# ALLPRINT-CAPBOARD-677512-DIGITAL-OUTPUTS.net
KiCad netlist of a schematic drawn in Altium Designer
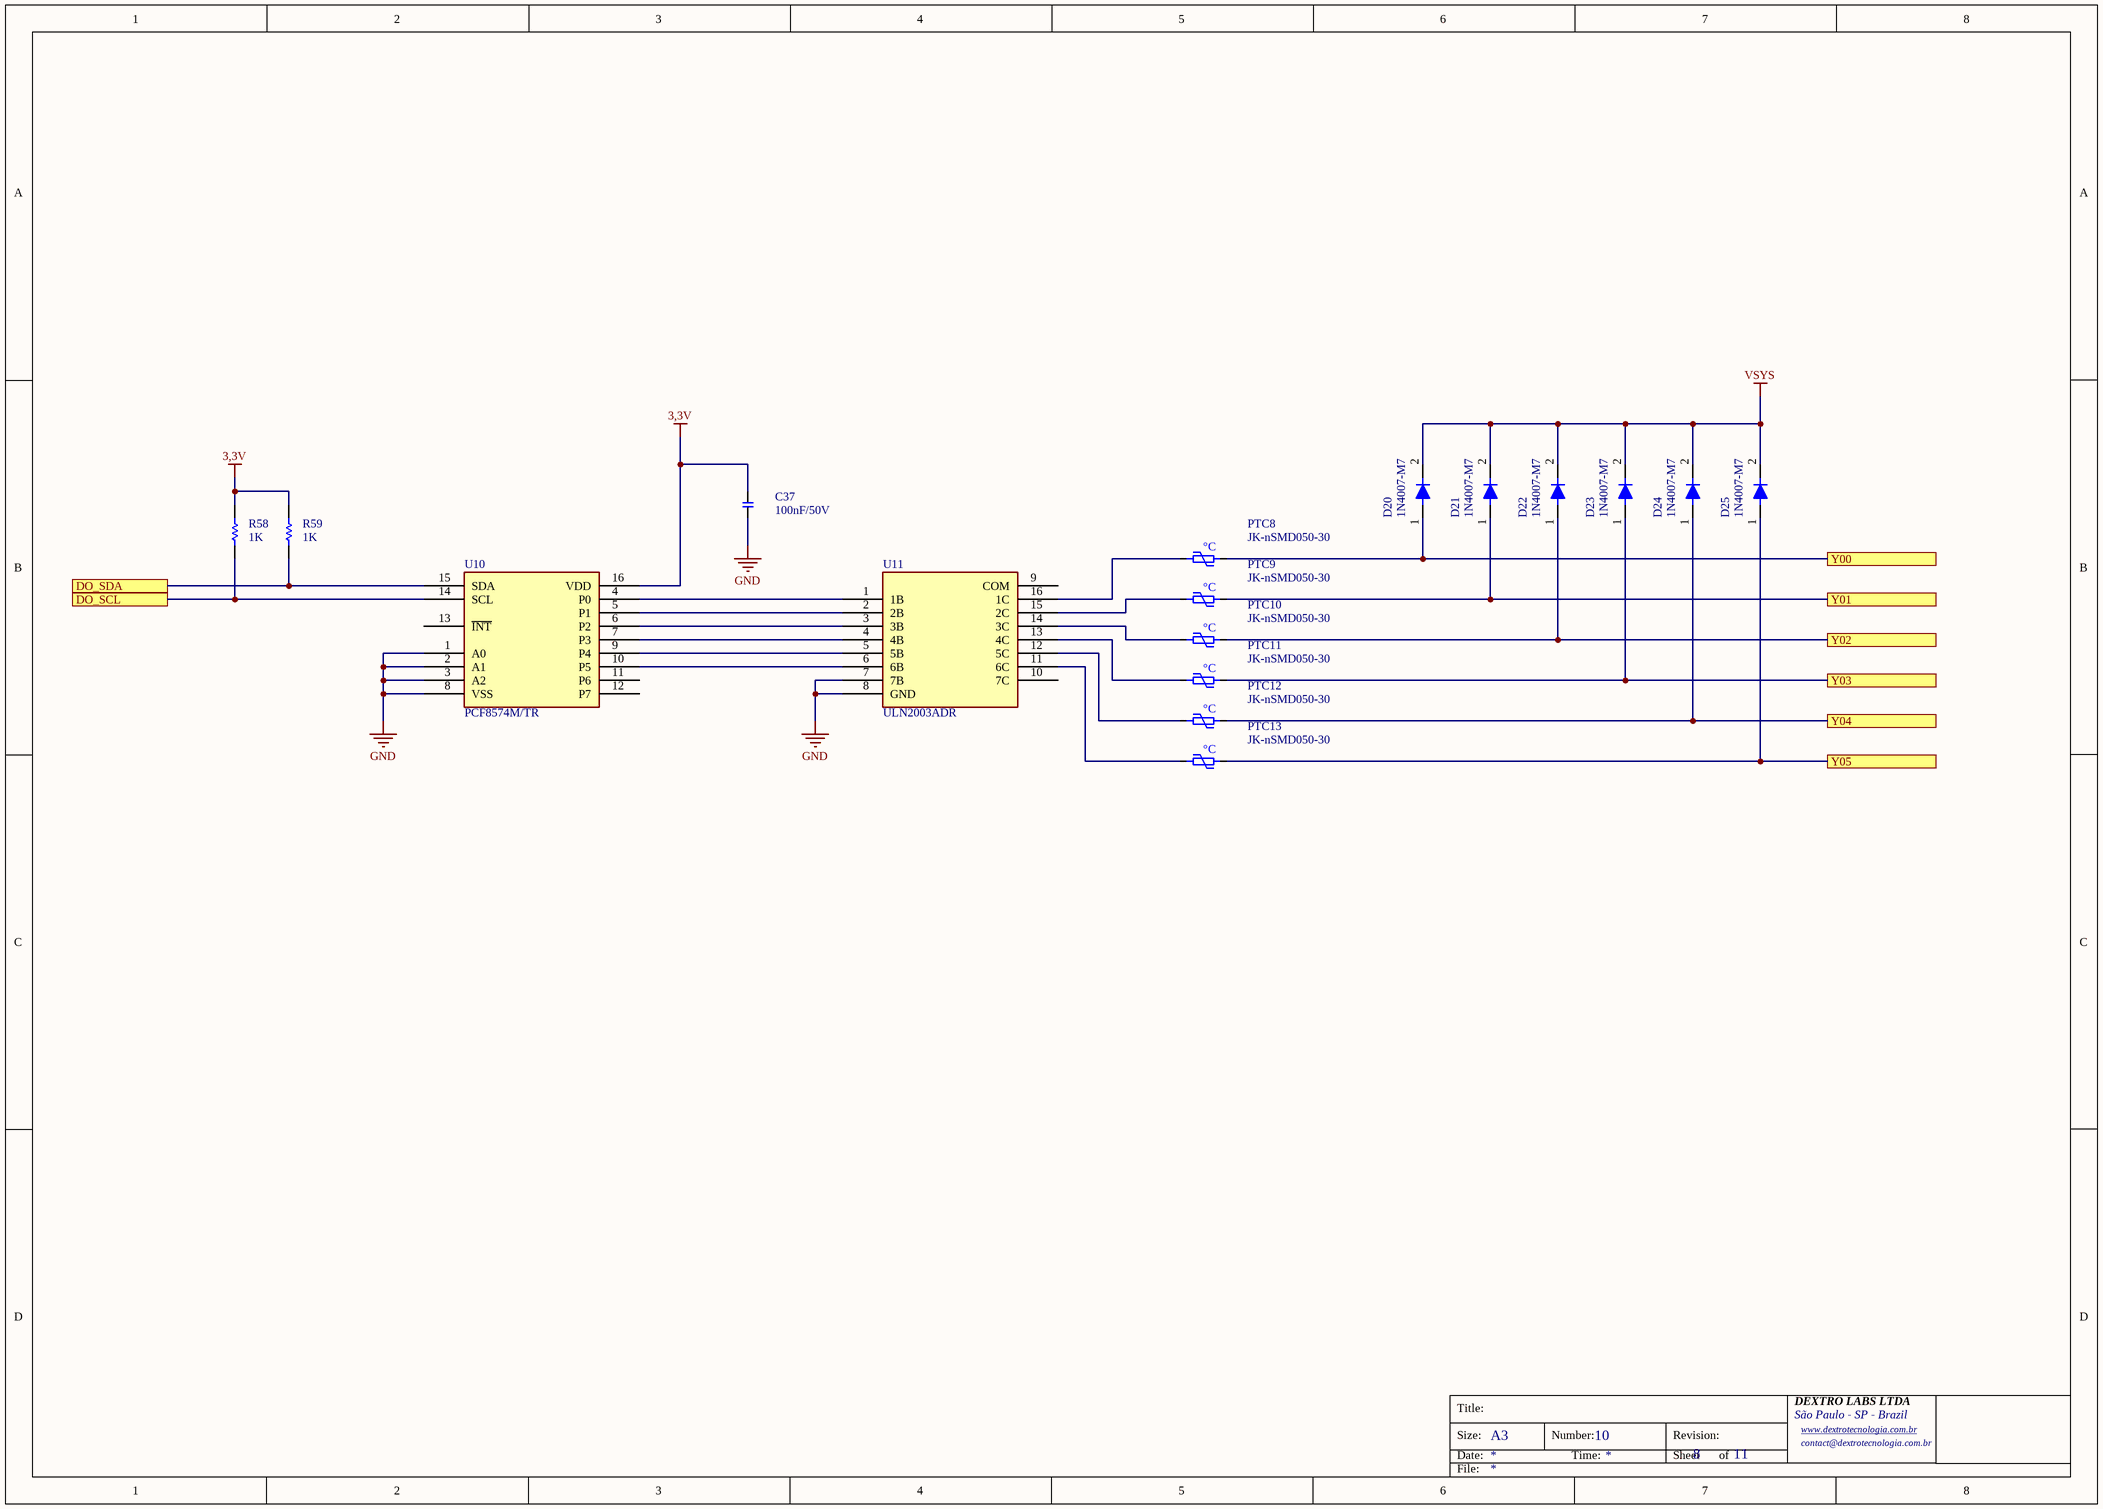
[diagram p0: ALLPRINT-CAPBOARD-677512-DIGITAL-OUTPUTS.SchDoc]

(export (version "E")
  (design (tool "Eeschema 10.0.6"))
  (components
    (comp (ref "C37")
      (value "100nF/50V")
      (footprint "CAP-0603")
      (description "50V 100nF X7R ±10% 0603 Multilayer Ceramic Capacitors MLCC - SMD/SMT ROHS")
      (libsource (lib "dextro-labs") (part "CAP-100nF/50V-0603-X7R-MLCC"))
    )
    (comp (ref "D20")
      (value "1N4007-M7")
      (footprint "SMA")
      (description "C20754788")
      (libsource (lib "dextro-labs") (part "1N4007-M7"))
    )
    (comp (ref "D21")
      (value "1N4007-M7")
      (footprint "SMA")
      (description "C20754788")
      (libsource (lib "dextro-labs") (part "1N4007-M7"))
    )
    (comp (ref "D22")
      (value "1N4007-M7")
      (footprint "SMA")
      (description "C20754788")
      (libsource (lib "dextro-labs") (part "1N4007-M7"))
    )
    (comp (ref "D23")
      (value "1N4007-M7")
      (footprint "SMA")
      (description "C20754788")
      (libsource (lib "dextro-labs") (part "1N4007-M7"))
    )
    (comp (ref "D24")
      (value "1N4007-M7")
      (footprint "SMA")
      (description "C20754788")
      (libsource (lib "dextro-labs") (part "1N4007-M7"))
    )
    (comp (ref "D25")
      (value "1N4007-M7")
      (footprint "SMA")
      (description "C20754788")
      (libsource (lib "dextro-labs") (part "1N4007-M7"))
    )
    (comp (ref "PTC8")
      (value "JK-nSMD050-30")
      (footprint "PTC-1206")
      (description "30V 500mA 100A 1A 150mΩ 1206 PTC Resettable Fuses ROHS")
      (libsource (lib "dextro-labs") (part "PTC-FUSE-30V-500mA-1206"))
    )
    (comp (ref "PTC9")
      (value "JK-nSMD050-30")
      (footprint "PTC-1206")
      (description "30V 500mA 100A 1A 150mΩ 1206 PTC Resettable Fuses ROHS")
      (libsource (lib "dextro-labs") (part "PTC-FUSE-30V-500mA-1206"))
    )
    (comp (ref "PTC10")
      (value "JK-nSMD050-30")
      (footprint "PTC-1206")
      (description "30V 500mA 100A 1A 150mΩ 1206 PTC Resettable Fuses ROHS")
      (libsource (lib "dextro-labs") (part "PTC-FUSE-30V-500mA-1206"))
    )
    (comp (ref "PTC11")
      (value "JK-nSMD050-30")
      (footprint "PTC-1206")
      (description "30V 500mA 100A 1A 150mΩ 1206 PTC Resettable Fuses ROHS")
      (libsource (lib "dextro-labs") (part "PTC-FUSE-30V-500mA-1206"))
    )
    (comp (ref "PTC12")
      (value "JK-nSMD050-30")
      (footprint "PTC-1206")
      (description "30V 500mA 100A 1A 150mΩ 1206 PTC Resettable Fuses ROHS")
      (libsource (lib "dextro-labs") (part "PTC-FUSE-30V-500mA-1206"))
    )
    (comp (ref "PTC13")
      (value "JK-nSMD050-30")
      (footprint "PTC-1206")
      (description "30V 500mA 100A 1A 150mΩ 1206 PTC Resettable Fuses ROHS")
      (libsource (lib "dextro-labs") (part "PTC-FUSE-30V-500mA-1206"))
    )
    (comp (ref "R58")
      (value "1K")
      (footprint "RES-0603")
      (description "100mW Thick Film Resistor 75V ±100ppm/℃ ±1% 1kΩ 0603 Chip Resistor - Surface Mount ROHS")
      (libsource (lib "dextro-labs") (part "RES-1K-1%-100mW-0603"))
    )
    (comp (ref "R59")
      (value "1K")
      (footprint "RES-0603")
      (description "100mW Thick Film Resistor 75V ±100ppm/℃ ±1% 1kΩ 0603 Chip Resistor - Surface Mount ROHS")
      (libsource (lib "dextro-labs") (part "RES-1K-1%-100mW-0603"))
    )
    (comp (ref "U10")
      (value "PCF8574M/TR")
      (footprint "SOIC-16-3D")
      (description "8 I2C SOP-16-150mil I/O Expanders RoHS")
      (libsource (lib "dextro-labs") (part "PCF8574M/TR"))
    )
    (comp (ref "U11")
      (value "ULN2003ADR")
      (footprint "SOIC-16-3D")
      (description "50V 500mA SOIC-16 Bipolar Transistor Arrays RoHS")
      (libsource (lib "dextro-labs") (part "ULN2003ADR"))
    )
  )
  (nets
    (net (code "1") (name "/DO_SCL") (class "Default")
      (node (ref "R58") (pin "1") (pinfunction "1_1") (pintype "passive"))
      (node (ref "U10") (pin "14") (pinfunction "SCL_14") (pintype "passive"))
    )
    (net (code "2") (name "/DO_SDA") (class "Default")
      (node (ref "R59") (pin "1") (pinfunction "1_1") (pintype "passive"))
      (node (ref "U10") (pin "15") (pinfunction "SDA_15") (pintype "passive"))
    )
    (net (code "3") (name "/Y00") (class "Default")
      (node (ref "D20") (pin "1") (pinfunction "A1_1") (pintype "passive"))
      (node (ref "PTC8") (pin "2") (pinfunction "2_2") (pintype "passive"))
    )
    (net (code "4") (name "/Y01") (class "Default")
      (node (ref "D21") (pin "1") (pinfunction "A1_1") (pintype "passive"))
      (node (ref "PTC9") (pin "2") (pinfunction "2_2") (pintype "passive"))
    )
    (net (code "5") (name "/Y02") (class "Default")
      (node (ref "D22") (pin "1") (pinfunction "A1_1") (pintype "passive"))
      (node (ref "PTC10") (pin "2") (pinfunction "2_2") (pintype "passive"))
    )
    (net (code "6") (name "/Y03") (class "Default")
      (node (ref "D23") (pin "1") (pinfunction "A1_1") (pintype "passive"))
      (node (ref "PTC11") (pin "2") (pinfunction "2_2") (pintype "passive"))
    )
    (net (code "7") (name "/Y04") (class "Default")
      (node (ref "D24") (pin "1") (pinfunction "A1_1") (pintype "passive"))
      (node (ref "PTC12") (pin "2") (pinfunction "2_2") (pintype "passive"))
    )
    (net (code "8") (name "/Y05") (class "Default")
      (node (ref "D25") (pin "1") (pinfunction "A1_1") (pintype "passive"))
      (node (ref "PTC13") (pin "2") (pinfunction "2_2") (pintype "passive"))
    )
    (net (code "9") (name "3,3V") (class "Default")
      (node (ref "C37") (pin "2") (pinfunction "2_2") (pintype "passive"))
      (node (ref "R58") (pin "2") (pinfunction "2_2") (pintype "passive"))
      (node (ref "R59") (pin "2") (pinfunction "2_2") (pintype "passive"))
      (node (ref "U10") (pin "16") (pinfunction "VDD_16") (pintype "passive"))
    )
    (net (code "10") (name "GND") (class "Default")
      (node (ref "C37") (pin "1") (pinfunction "1_1") (pintype "passive"))
      (node (ref "U10") (pin "1") (pinfunction "A0_1") (pintype "passive"))
      (node (ref "U10") (pin "2") (pinfunction "A1_2") (pintype "passive"))
      (node (ref "U10") (pin "3") (pinfunction "A2_3") (pintype "passive"))
      (node (ref "U10") (pin "8") (pinfunction "VSS_8") (pintype "passive"))
      (node (ref "U11") (pin "7") (pinfunction "7B_7") (pintype "passive"))
      (node (ref "U11") (pin "8") (pinfunction "GND_8") (pintype "passive"))
    )
    (net (code "11") (name "Net-(U10-P0)") (class "Default")
      (node (ref "U10") (pin "4") (pinfunction "P0_4") (pintype "passive"))
      (node (ref "U11") (pin "1") (pinfunction "1B_1") (pintype "passive"))
    )
    (net (code "12") (name "Net-(U10-P1)") (class "Default")
      (node (ref "U10") (pin "5") (pinfunction "P1_5") (pintype "passive"))
      (node (ref "U11") (pin "2") (pinfunction "2B_2") (pintype "passive"))
    )
    (net (code "13") (name "Net-(U10-P2)") (class "Default")
      (node (ref "U10") (pin "6") (pinfunction "P2_6") (pintype "passive"))
      (node (ref "U11") (pin "3") (pinfunction "3B_3") (pintype "passive"))
    )
    (net (code "14") (name "Net-(U10-P3)") (class "Default")
      (node (ref "U10") (pin "7") (pinfunction "P3_7") (pintype "passive"))
      (node (ref "U11") (pin "4") (pinfunction "4B_4") (pintype "passive"))
    )
    (net (code "15") (name "Net-(U10-P4)") (class "Default")
      (node (ref "U10") (pin "9") (pinfunction "P4_9") (pintype "passive"))
      (node (ref "U11") (pin "5") (pinfunction "5B_5") (pintype "passive"))
    )
    (net (code "16") (name "Net-(U10-P5)") (class "Default")
      (node (ref "U10") (pin "10") (pinfunction "P5_10") (pintype "passive"))
      (node (ref "U11") (pin "6") (pinfunction "6B_6") (pintype "passive"))
    )
    (net (code "17") (name "Net-(U11-1C)") (class "Default")
      (node (ref "PTC8") (pin "1") (pinfunction "1_1") (pintype "passive"))
      (node (ref "U11") (pin "16") (pinfunction "1C_16") (pintype "passive"))
    )
    (net (code "18") (name "Net-(U11-2C)") (class "Default")
      (node (ref "PTC9") (pin "1") (pinfunction "1_1") (pintype "passive"))
      (node (ref "U11") (pin "15") (pinfunction "2C_15") (pintype "passive"))
    )
    (net (code "19") (name "Net-(U11-3C)") (class "Default")
      (node (ref "PTC10") (pin "1") (pinfunction "1_1") (pintype "passive"))
      (node (ref "U11") (pin "14") (pinfunction "3C_14") (pintype "passive"))
    )
    (net (code "20") (name "Net-(U11-4C)") (class "Default")
      (node (ref "PTC11") (pin "1") (pinfunction "1_1") (pintype "passive"))
      (node (ref "U11") (pin "13") (pinfunction "4C_13") (pintype "passive"))
    )
    (net (code "21") (name "Net-(U11-5C)") (class "Default")
      (node (ref "PTC12") (pin "1") (pinfunction "1_1") (pintype "passive"))
      (node (ref "U11") (pin "12") (pinfunction "5C_12") (pintype "passive"))
    )
    (net (code "22") (name "Net-(U11-6C)") (class "Default")
      (node (ref "PTC13") (pin "1") (pinfunction "1_1") (pintype "passive"))
      (node (ref "U11") (pin "11") (pinfunction "6C_11") (pintype "passive"))
    )
    (net (code "23") (name "VSYS") (class "Default")
      (node (ref "D20") (pin "2") (pinfunction "K_2") (pintype "passive"))
      (node (ref "D21") (pin "2") (pinfunction "K_2") (pintype "passive"))
      (node (ref "D22") (pin "2") (pinfunction "K_2") (pintype "passive"))
      (node (ref "D23") (pin "2") (pinfunction "K_2") (pintype "passive"))
      (node (ref "D24") (pin "2") (pinfunction "K_2") (pintype "passive"))
      (node (ref "D25") (pin "2") (pinfunction "K_2") (pintype "passive"))
    )
    (net (code "24") (name "unconnected-(U10-P6-Pad11)") (class "Default")
      (node (ref "U10") (pin "11") (pinfunction "P6_11") (pintype "passive"))
    )
    (net (code "25") (name "unconnected-(U10-P7-Pad12)") (class "Default")
      (node (ref "U10") (pin "12") (pinfunction "P7_12") (pintype "passive"))
    )
    (net (code "26") (name "unconnected-(U10-~{INT}-Pad13)") (class "Default")
      (node (ref "U10") (pin "13") (pinfunction "~{INT}_13") (pintype "passive"))
    )
    (net (code "27") (name "unconnected-(U11-7C-Pad10)") (class "Default")
      (node (ref "U11") (pin "10") (pinfunction "7C_10") (pintype "passive"))
    )
    (net (code "28") (name "unconnected-(U11-COM-Pad9)") (class "Default")
      (node (ref "U11") (pin "9") (pinfunction "COM_9") (pintype "passive"))
    )
  )
)
